# 2016ship.net
KiCad netlist of a schematic drawn in Altium Designer
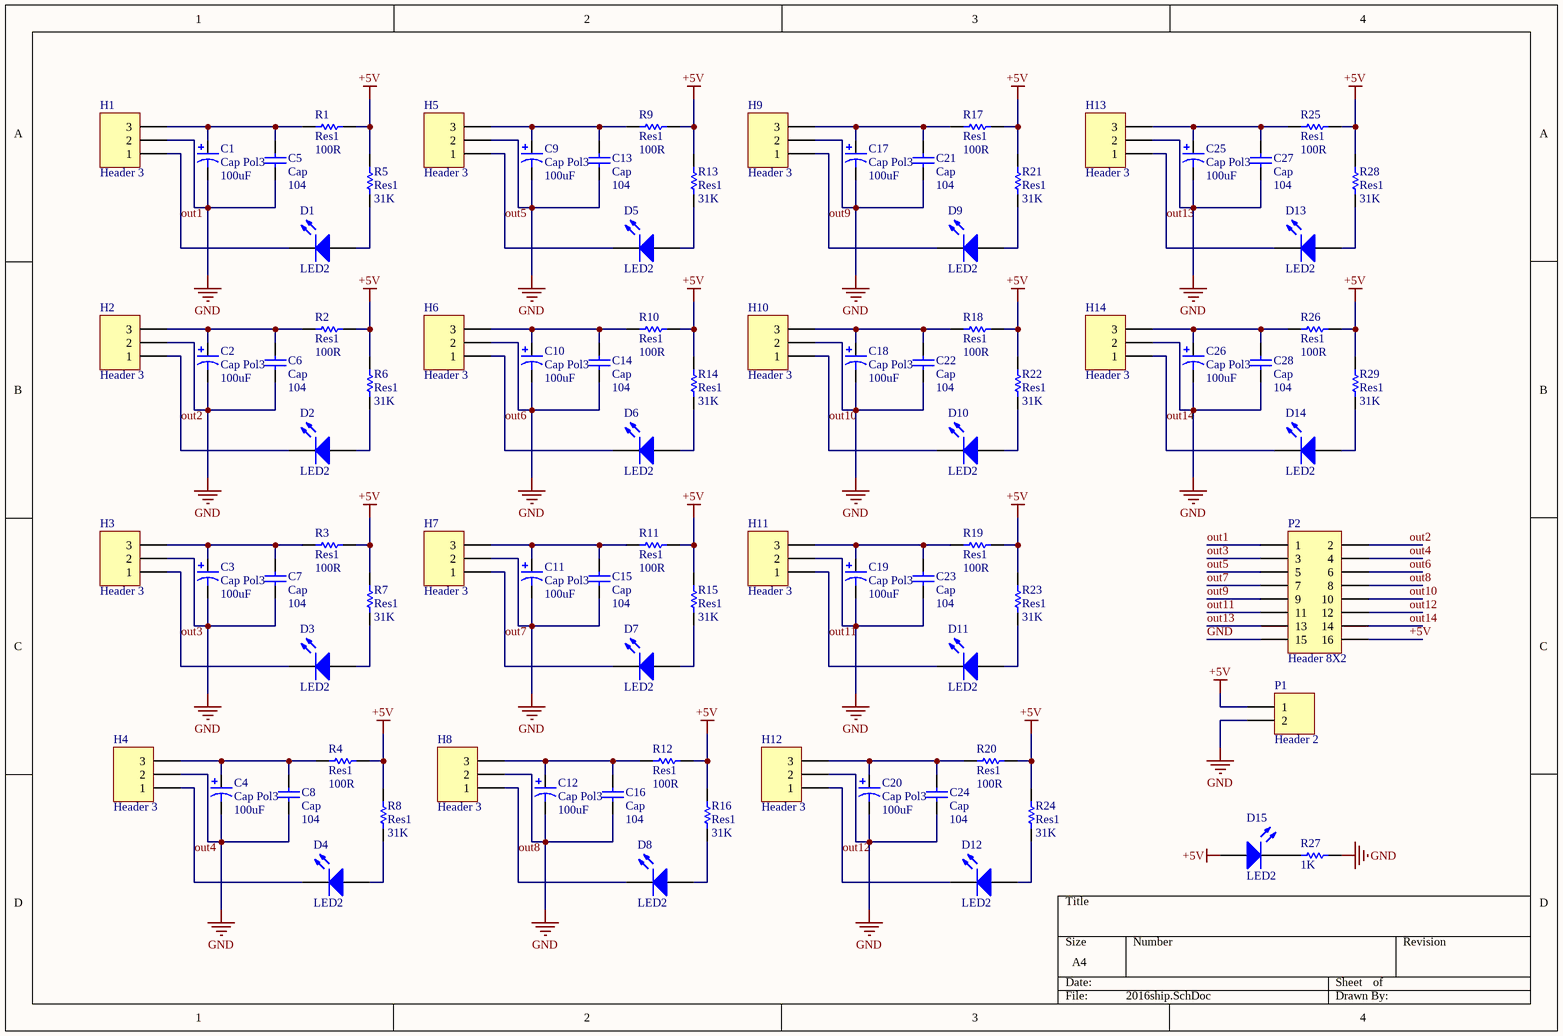
[diagram p0: 2016ship.SchDoc]

(export (version "E")
  (design (tool "Eeschema 10.0.6"))
  (components
    (comp (ref "C1")
      (value "Cap Pol3")
      (footprint "7343")
      (description "Polarized Capacitor (Surface Mount)")
      (fields (field (name "ALTIUM_VALUE") "100uF") (field (name "PUBLISHER") "Altium Limited"))
      (libsource (lib "Miscellaneous Devices") (part "Cap Pol3"))
    )
    (comp (ref "C2")
      (value "Cap Pol3")
      (footprint "7343")
      (description "Polarized Capacitor (Surface Mount)")
      (fields (field (name "ALTIUM_VALUE") "100uF") (field (name "PUBLISHER") "Altium Limited"))
      (libsource (lib "Miscellaneous Devices") (part "Cap Pol3"))
    )
    (comp (ref "C3")
      (value "Cap Pol3")
      (footprint "7343")
      (description "Polarized Capacitor (Surface Mount)")
      (fields (field (name "ALTIUM_VALUE") "100uF") (field (name "PUBLISHER") "Altium Limited"))
      (libsource (lib "Miscellaneous Devices") (part "Cap Pol3"))
    )
    (comp (ref "C4")
      (value "Cap Pol3")
      (footprint "7343")
      (description "Polarized Capacitor (Surface Mount)")
      (fields (field (name "ALTIUM_VALUE") "100uF") (field (name "PUBLISHER") "Altium Limited"))
      (libsource (lib "Miscellaneous Devices") (part "Cap Pol3"))
    )
    (comp (ref "C5")
      (value "Cap")
      (footprint "0805C")
      (description "Capacitor")
      (fields (field (name "ALTIUM_VALUE") "104") (field (name "PUBLISHER") "Altium Limited"))
      (libsource (lib "Miscellaneous Devices") (part "Cap"))
    )
    (comp (ref "C6")
      (value "Cap")
      (footprint "0805C")
      (description "Capacitor")
      (fields (field (name "ALTIUM_VALUE") "104") (field (name "PUBLISHER") "Altium Limited"))
      (libsource (lib "Miscellaneous Devices") (part "Cap"))
    )
    (comp (ref "C7")
      (value "Cap")
      (footprint "0805C")
      (description "Capacitor")
      (fields (field (name "ALTIUM_VALUE") "104") (field (name "PUBLISHER") "Altium Limited"))
      (libsource (lib "Miscellaneous Devices") (part "Cap"))
    )
    (comp (ref "C8")
      (value "Cap")
      (footprint "0805C")
      (description "Capacitor")
      (fields (field (name "ALTIUM_VALUE") "104") (field (name "PUBLISHER") "Altium Limited"))
      (libsource (lib "Miscellaneous Devices") (part "Cap"))
    )
    (comp (ref "C9")
      (value "Cap Pol3")
      (footprint "7343")
      (description "Polarized Capacitor (Surface Mount)")
      (fields (field (name "ALTIUM_VALUE") "100uF") (field (name "PUBLISHER") "Altium Limited"))
      (libsource (lib "Miscellaneous Devices") (part "Cap Pol3"))
    )
    (comp (ref "C10")
      (value "Cap Pol3")
      (footprint "7343")
      (description "Polarized Capacitor (Surface Mount)")
      (fields (field (name "ALTIUM_VALUE") "100uF") (field (name "PUBLISHER") "Altium Limited"))
      (libsource (lib "Miscellaneous Devices") (part "Cap Pol3"))
    )
    (comp (ref "C11")
      (value "Cap Pol3")
      (footprint "7343")
      (description "Polarized Capacitor (Surface Mount)")
      (fields (field (name "ALTIUM_VALUE") "100uF") (field (name "PUBLISHER") "Altium Limited"))
      (libsource (lib "Miscellaneous Devices") (part "Cap Pol3"))
    )
    (comp (ref "C12")
      (value "Cap Pol3")
      (footprint "7343")
      (description "Polarized Capacitor (Surface Mount)")
      (fields (field (name "ALTIUM_VALUE") "100uF") (field (name "PUBLISHER") "Altium Limited"))
      (libsource (lib "Miscellaneous Devices") (part "Cap Pol3"))
    )
    (comp (ref "C13")
      (value "Cap")
      (footprint "0805C")
      (description "Capacitor")
      (fields (field (name "ALTIUM_VALUE") "104") (field (name "PUBLISHER") "Altium Limited"))
      (libsource (lib "Miscellaneous Devices") (part "Cap"))
    )
    (comp (ref "C14")
      (value "Cap")
      (footprint "0805c")
      (description "Capacitor")
      (fields (field (name "ALTIUM_VALUE") "104") (field (name "PUBLISHER") "Altium Limited"))
      (libsource (lib "Miscellaneous Devices") (part "Cap"))
    )
    (comp (ref "C15")
      (value "Cap")
      (footprint "0805C")
      (description "Capacitor")
      (fields (field (name "ALTIUM_VALUE") "104") (field (name "PUBLISHER") "Altium Limited"))
      (libsource (lib "Miscellaneous Devices") (part "Cap"))
    )
    (comp (ref "C16")
      (value "Cap")
      (footprint "0805C")
      (description "Capacitor")
      (fields (field (name "ALTIUM_VALUE") "104") (field (name "PUBLISHER") "Altium Limited"))
      (libsource (lib "Miscellaneous Devices") (part "Cap"))
    )
    (comp (ref "C17")
      (value "Cap Pol3")
      (footprint "7343")
      (description "Polarized Capacitor (Surface Mount)")
      (fields (field (name "ALTIUM_VALUE") "100uF") (field (name "PUBLISHER") "Altium Limited"))
      (libsource (lib "Miscellaneous Devices") (part "Cap Pol3"))
    )
    (comp (ref "C18")
      (value "Cap Pol3")
      (footprint "7343")
      (description "Polarized Capacitor (Surface Mount)")
      (fields (field (name "ALTIUM_VALUE") "100uF") (field (name "PUBLISHER") "Altium Limited"))
      (libsource (lib "Miscellaneous Devices") (part "Cap Pol3"))
    )
    (comp (ref "C19")
      (value "Cap Pol3")
      (footprint "7343")
      (description "Polarized Capacitor (Surface Mount)")
      (fields (field (name "ALTIUM_VALUE") "100uF") (field (name "PUBLISHER") "Altium Limited"))
      (libsource (lib "Miscellaneous Devices") (part "Cap Pol3"))
    )
    (comp (ref "C20")
      (value "Cap Pol3")
      (footprint "7343")
      (description "Polarized Capacitor (Surface Mount)")
      (fields (field (name "ALTIUM_VALUE") "100uF") (field (name "PUBLISHER") "Altium Limited"))
      (libsource (lib "Miscellaneous Devices") (part "Cap Pol3"))
    )
    (comp (ref "C21")
      (value "Cap")
      (footprint "0805C")
      (description "Capacitor")
      (fields (field (name "ALTIUM_VALUE") "104") (field (name "PUBLISHER") "Altium Limited"))
      (libsource (lib "Miscellaneous Devices") (part "Cap"))
    )
    (comp (ref "C22")
      (value "Cap")
      (footprint "0805C")
      (description "Capacitor")
      (fields (field (name "ALTIUM_VALUE") "104") (field (name "PUBLISHER") "Altium Limited"))
      (libsource (lib "Miscellaneous Devices") (part "Cap"))
    )
    (comp (ref "C23")
      (value "Cap")
      (footprint "0805C")
      (description "Capacitor")
      (fields (field (name "ALTIUM_VALUE") "104") (field (name "PUBLISHER") "Altium Limited"))
      (libsource (lib "Miscellaneous Devices") (part "Cap"))
    )
    (comp (ref "C24")
      (value "Cap")
      (footprint "0805C")
      (description "Capacitor")
      (fields (field (name "ALTIUM_VALUE") "104") (field (name "PUBLISHER") "Altium Limited"))
      (libsource (lib "Miscellaneous Devices") (part "Cap"))
    )
    (comp (ref "C25")
      (value "Cap Pol3")
      (footprint "7343")
      (description "Polarized Capacitor (Surface Mount)")
      (fields (field (name "ALTIUM_VALUE") "100uF") (field (name "PUBLISHER") "Altium Limited"))
      (libsource (lib "Miscellaneous Devices") (part "Cap Pol3"))
    )
    (comp (ref "C26")
      (value "Cap Pol3")
      (footprint "7343")
      (description "Polarized Capacitor (Surface Mount)")
      (fields (field (name "ALTIUM_VALUE") "100uF") (field (name "PUBLISHER") "Altium Limited"))
      (libsource (lib "Miscellaneous Devices") (part "Cap Pol3"))
    )
    (comp (ref "C27")
      (value "Cap")
      (footprint "0805C")
      (description "Capacitor")
      (fields (field (name "ALTIUM_VALUE") "104") (field (name "PUBLISHER") "Altium Limited"))
      (libsource (lib "Miscellaneous Devices") (part "Cap"))
    )
    (comp (ref "C28")
      (value "Cap")
      (footprint "0805C")
      (description "Capacitor")
      (fields (field (name "ALTIUM_VALUE") "104") (field (name "PUBLISHER") "Altium Limited"))
      (libsource (lib "Miscellaneous Devices") (part "Cap"))
    )
    (comp (ref "D1")
      (value "LED2")
      (footprint "LED-0805")
      (description "Typical RED, GREEN, YELLOW, AMBER GaAs LED")
      (fields (field (name "PUBLISHER") "Altium Limited"))
      (libsource (lib "Miscellaneous Devices") (part "LED2"))
    )
    (comp (ref "D2")
      (value "LED2")
      (footprint "LED-0805")
      (description "Typical RED, GREEN, YELLOW, AMBER GaAs LED")
      (fields (field (name "PUBLISHER") "Altium Limited"))
      (libsource (lib "Miscellaneous Devices") (part "LED2"))
    )
    (comp (ref "D3")
      (value "LED2")
      (footprint "LED-0805")
      (description "Typical RED, GREEN, YELLOW, AMBER GaAs LED")
      (fields (field (name "PUBLISHER") "Altium Limited"))
      (libsource (lib "Miscellaneous Devices") (part "LED2"))
    )
    (comp (ref "D4")
      (value "LED2")
      (footprint "LED-0805")
      (description "Typical RED, GREEN, YELLOW, AMBER GaAs LED")
      (fields (field (name "PUBLISHER") "Altium Limited"))
      (libsource (lib "Miscellaneous Devices") (part "LED2"))
    )
    (comp (ref "D5")
      (value "LED2")
      (footprint "LED-0805")
      (description "Typical RED, GREEN, YELLOW, AMBER GaAs LED")
      (fields (field (name "PUBLISHER") "Altium Limited"))
      (libsource (lib "Miscellaneous Devices") (part "LED2"))
    )
    (comp (ref "D6")
      (value "LED2")
      (footprint "LED-0805")
      (description "Typical RED, GREEN, YELLOW, AMBER GaAs LED")
      (fields (field (name "PUBLISHER") "Altium Limited"))
      (libsource (lib "Miscellaneous Devices") (part "LED2"))
    )
    (comp (ref "D7")
      (value "LED2")
      (footprint "LED-0805")
      (description "Typical RED, GREEN, YELLOW, AMBER GaAs LED")
      (fields (field (name "PUBLISHER") "Altium Limited"))
      (libsource (lib "Miscellaneous Devices") (part "LED2"))
    )
    (comp (ref "D8")
      (value "LED2")
      (footprint "LED-0805")
      (description "Typical RED, GREEN, YELLOW, AMBER GaAs LED")
      (fields (field (name "PUBLISHER") "Altium Limited"))
      (libsource (lib "Miscellaneous Devices") (part "LED2"))
    )
    (comp (ref "D9")
      (value "LED2")
      (footprint "LED-0805")
      (description "Typical RED, GREEN, YELLOW, AMBER GaAs LED")
      (fields (field (name "PUBLISHER") "Altium Limited"))
      (libsource (lib "Miscellaneous Devices") (part "LED2"))
    )
    (comp (ref "D10")
      (value "LED2")
      (footprint "LED-0805")
      (description "Typical RED, GREEN, YELLOW, AMBER GaAs LED")
      (fields (field (name "PUBLISHER") "Altium Limited"))
      (libsource (lib "Miscellaneous Devices") (part "LED2"))
    )
    (comp (ref "D11")
      (value "LED2")
      (footprint "LED-0805")
      (description "Typical RED, GREEN, YELLOW, AMBER GaAs LED")
      (fields (field (name "PUBLISHER") "Altium Limited"))
      (libsource (lib "Miscellaneous Devices") (part "LED2"))
    )
    (comp (ref "D12")
      (value "LED2")
      (footprint "LED-0805")
      (description "Typical RED, GREEN, YELLOW, AMBER GaAs LED")
      (fields (field (name "PUBLISHER") "Altium Limited"))
      (libsource (lib "Miscellaneous Devices") (part "LED2"))
    )
    (comp (ref "D13")
      (value "LED2")
      (footprint "LED-0805")
      (description "Typical RED, GREEN, YELLOW, AMBER GaAs LED")
      (fields (field (name "PUBLISHER") "Altium Limited"))
      (libsource (lib "Miscellaneous Devices") (part "LED2"))
    )
    (comp (ref "D14")
      (value "LED2")
      (footprint "LED-0805")
      (description "Typical RED, GREEN, YELLOW, AMBER GaAs LED")
      (fields (field (name "PUBLISHER") "Altium Limited"))
      (libsource (lib "Miscellaneous Devices") (part "LED2"))
    )
    (comp (ref "D15")
      (value "LED2")
      (footprint "LED-0805")
      (description "Typical RED, GREEN, YELLOW, AMBER GaAs LED")
      (fields (field (name "PUBLISHER") "Altium Limited"))
      (libsource (lib "Miscellaneous Devices") (part "LED2"))
    )
    (comp (ref "H1")
      (value "Header 3")
      (footprint "HDR1X3")
      (description "Header, 3-Pin")
      (fields (field (name "PUBLISHER") "Altium Limited"))
      (libsource (lib "Miscellaneous Connectors") (part "Header 3"))
    )
    (comp (ref "H2")
      (value "Header 3")
      (footprint "HDR1X3")
      (description "Header, 3-Pin")
      (fields (field (name "PUBLISHER") "Altium Limited"))
      (libsource (lib "Miscellaneous Connectors") (part "Header 3"))
    )
    (comp (ref "H3")
      (value "Header 3")
      (footprint "HDR1X3")
      (description "Header, 3-Pin")
      (fields (field (name "PUBLISHER") "Altium Limited"))
      (libsource (lib "Miscellaneous Connectors") (part "Header 3"))
    )
    (comp (ref "H4")
      (value "Header 3")
      (footprint "HDR1X3")
      (description "Header, 3-Pin")
      (fields (field (name "PUBLISHER") "Altium Limited"))
      (libsource (lib "Miscellaneous Connectors") (part "Header 3"))
    )
    (comp (ref "H5")
      (value "Header 3")
      (footprint "HDR1X3")
      (description "Header, 3-Pin")
      (fields (field (name "PUBLISHER") "Altium Limited"))
      (libsource (lib "Miscellaneous Connectors") (part "Header 3"))
    )
    (comp (ref "H6")
      (value "Header 3")
      (footprint "HDR1X3")
      (description "Header, 3-Pin")
      (fields (field (name "PUBLISHER") "Altium Limited"))
      (libsource (lib "Miscellaneous Connectors") (part "Header 3"))
    )
    (comp (ref "H7")
      (value "Header 3")
      (footprint "HDR1X3")
      (description "Header, 3-Pin")
      (fields (field (name "PUBLISHER") "Altium Limited"))
      (libsource (lib "Miscellaneous Connectors") (part "Header 3"))
    )
    (comp (ref "H8")
      (value "Header 3")
      (footprint "HDR1X3")
      (description "Header, 3-Pin")
      (fields (field (name "PUBLISHER") "Altium Limited"))
      (libsource (lib "Miscellaneous Connectors") (part "Header 3"))
    )
    (comp (ref "H9")
      (value "Header 3")
      (footprint "HDR1X3")
      (description "Header, 3-Pin")
      (fields (field (name "PUBLISHER") "Altium Limited"))
      (libsource (lib "Miscellaneous Connectors") (part "Header 3"))
    )
    (comp (ref "H10")
      (value "Header 3")
      (footprint "HDR1X3")
      (description "Header, 3-Pin")
      (fields (field (name "PUBLISHER") "Altium Limited"))
      (libsource (lib "Miscellaneous Connectors") (part "Header 3"))
    )
    (comp (ref "H11")
      (value "Header 3")
      (footprint "HDR1X3")
      (description "Header, 3-Pin")
      (fields (field (name "PUBLISHER") "Altium Limited"))
      (libsource (lib "Miscellaneous Connectors") (part "Header 3"))
    )
    (comp (ref "H12")
      (value "Header 3")
      (footprint "HDR1X3")
      (description "Header, 3-Pin")
      (fields (field (name "PUBLISHER") "Altium Limited"))
      (libsource (lib "Miscellaneous Connectors") (part "Header 3"))
    )
    (comp (ref "H13")
      (value "Header 3")
      (footprint "HDR1X3")
      (description "Header, 3-Pin")
      (fields (field (name "PUBLISHER") "Altium Limited"))
      (libsource (lib "Miscellaneous Connectors") (part "Header 3"))
    )
    (comp (ref "H14")
      (value "Header 3")
      (footprint "HDR1X3")
      (description "Header, 3-Pin")
      (fields (field (name "PUBLISHER") "Altium Limited"))
      (libsource (lib "Miscellaneous Connectors") (part "Header 3"))
    )
    (comp (ref "P1")
      (value "Header 2")
      (footprint "HDR1X2")
      (description "Header, 2-Pin")
      (fields (field (name "PUBLISHER") "Altium Limited"))
      (libsource (lib "Miscellaneous Connectors") (part "Header 2"))
    )
    (comp (ref "P2")
      (value "Header 8X2")
      (footprint "HDR2X8")
      (description "Header, 8-Pin, Dual row")
      (fields (field (name "PUBLISHER") "Altium Limited"))
      (libsource (lib "Miscellaneous Connectors") (part "Header 8X2"))
    )
    (comp (ref "R1")
      (value "Res1")
      (footprint "0805R")
      (description "Resistor")
      (fields (field (name "ALTIUM_VALUE") "100R") (field (name "PUBLISHER") "Altium Limited"))
      (libsource (lib "Miscellaneous Devices") (part "Res1"))
    )
    (comp (ref "R2")
      (value "Res1")
      (footprint "0805R")
      (description "Resistor")
      (fields (field (name "ALTIUM_VALUE") "100R") (field (name "PUBLISHER") "Altium Limited"))
      (libsource (lib "Miscellaneous Devices") (part "Res1"))
    )
    (comp (ref "R3")
      (value "Res1")
      (footprint "0805R")
      (description "Resistor")
      (fields (field (name "ALTIUM_VALUE") "100R") (field (name "PUBLISHER") "Altium Limited"))
      (libsource (lib "Miscellaneous Devices") (part "Res1"))
    )
    (comp (ref "R4")
      (value "Res1")
      (footprint "0805R")
      (description "Resistor")
      (fields (field (name "ALTIUM_VALUE") "100R") (field (name "PUBLISHER") "Altium Limited"))
      (libsource (lib "Miscellaneous Devices") (part "Res1"))
    )
    (comp (ref "R5")
      (value "Res1")
      (footprint "0805R")
      (description "Resistor")
      (fields (field (name "ALTIUM_VALUE") "31K") (field (name "PUBLISHER") "Altium Limited"))
      (libsource (lib "Miscellaneous Devices") (part "Res1"))
    )
    (comp (ref "R6")
      (value "Res1")
      (footprint "0805R")
      (description "Resistor")
      (fields (field (name "ALTIUM_VALUE") "31K") (field (name "PUBLISHER") "Altium Limited"))
      (libsource (lib "Miscellaneous Devices") (part "Res1"))
    )
    (comp (ref "R7")
      (value "Res1")
      (footprint "0805R")
      (description "Resistor")
      (fields (field (name "ALTIUM_VALUE") "31K") (field (name "PUBLISHER") "Altium Limited"))
      (libsource (lib "Miscellaneous Devices") (part "Res1"))
    )
    (comp (ref "R8")
      (value "Res1")
      (footprint "0805R")
      (description "Resistor")
      (fields (field (name "ALTIUM_VALUE") "31K") (field (name "PUBLISHER") "Altium Limited"))
      (libsource (lib "Miscellaneous Devices") (part "Res1"))
    )
    (comp (ref "R9")
      (value "Res1")
      (footprint "0805R")
      (description "Resistor")
      (fields (field (name "ALTIUM_VALUE") "100R") (field (name "PUBLISHER") "Altium Limited"))
      (libsource (lib "Miscellaneous Devices") (part "Res1"))
    )
    (comp (ref "R10")
      (value "Res1")
      (footprint "0805R")
      (description "Resistor")
      (fields (field (name "ALTIUM_VALUE") "100R") (field (name "PUBLISHER") "Altium Limited"))
      (libsource (lib "Miscellaneous Devices") (part "Res1"))
    )
    (comp (ref "R11")
      (value "Res1")
      (footprint "0805R")
      (description "Resistor")
      (fields (field (name "ALTIUM_VALUE") "100R") (field (name "PUBLISHER") "Altium Limited"))
      (libsource (lib "Miscellaneous Devices") (part "Res1"))
    )
    (comp (ref "R12")
      (value "Res1")
      (footprint "0805R")
      (description "Resistor")
      (fields (field (name "ALTIUM_VALUE") "100R") (field (name "PUBLISHER") "Altium Limited"))
      (libsource (lib "Miscellaneous Devices") (part "Res1"))
    )
    (comp (ref "R13")
      (value "Res1")
      (footprint "0805R")
      (description "Resistor")
      (fields (field (name "ALTIUM_VALUE") "31K") (field (name "PUBLISHER") "Altium Limited"))
      (libsource (lib "Miscellaneous Devices") (part "Res1"))
    )
    (comp (ref "R14")
      (value "Res1")
      (footprint "0805R")
      (description "Resistor")
      (fields (field (name "ALTIUM_VALUE") "31K") (field (name "PUBLISHER") "Altium Limited"))
      (libsource (lib "Miscellaneous Devices") (part "Res1"))
    )
    (comp (ref "R15")
      (value "Res1")
      (footprint "0805R")
      (description "Resistor")
      (fields (field (name "ALTIUM_VALUE") "31K") (field (name "PUBLISHER") "Altium Limited"))
      (libsource (lib "Miscellaneous Devices") (part "Res1"))
    )
    (comp (ref "R16")
      (value "Res1")
      (footprint "0805R")
      (description "Resistor")
      (fields (field (name "ALTIUM_VALUE") "31K") (field (name "PUBLISHER") "Altium Limited"))
      (libsource (lib "Miscellaneous Devices") (part "Res1"))
    )
    (comp (ref "R17")
      (value "Res1")
      (footprint "0805R")
      (description "Resistor")
      (fields (field (name "ALTIUM_VALUE") "100R") (field (name "PUBLISHER") "Altium Limited"))
      (libsource (lib "Miscellaneous Devices") (part "Res1"))
    )
    (comp (ref "R18")
      (value "Res1")
      (footprint "0805R")
      (description "Resistor")
      (fields (field (name "ALTIUM_VALUE") "100R") (field (name "PUBLISHER") "Altium Limited"))
      (libsource (lib "Miscellaneous Devices") (part "Res1"))
    )
    (comp (ref "R19")
      (value "Res1")
      (footprint "0805R")
      (description "Resistor")
      (fields (field (name "ALTIUM_VALUE") "100R") (field (name "PUBLISHER") "Altium Limited"))
      (libsource (lib "Miscellaneous Devices") (part "Res1"))
    )
    (comp (ref "R20")
      (value "Res1")
      (footprint "0805R")
      (description "Resistor")
      (fields (field (name "ALTIUM_VALUE") "100R") (field (name "PUBLISHER") "Altium Limited"))
      (libsource (lib "Miscellaneous Devices") (part "Res1"))
    )
    (comp (ref "R21")
      (value "Res1")
      (footprint "0805R")
      (description "Resistor")
      (fields (field (name "ALTIUM_VALUE") "31K") (field (name "PUBLISHER") "Altium Limited"))
      (libsource (lib "Miscellaneous Devices") (part "Res1"))
    )
    (comp (ref "R22")
      (value "Res1")
      (footprint "0805R")
      (description "Resistor")
      (fields (field (name "ALTIUM_VALUE") "31K") (field (name "PUBLISHER") "Altium Limited"))
      (libsource (lib "Miscellaneous Devices") (part "Res1"))
    )
    (comp (ref "R23")
      (value "Res1")
      (footprint "0805R")
      (description "Resistor")
      (fields (field (name "ALTIUM_VALUE") "31K") (field (name "PUBLISHER") "Altium Limited"))
      (libsource (lib "Miscellaneous Devices") (part "Res1"))
    )
    (comp (ref "R24")
      (value "Res1")
      (footprint "0805R")
      (description "Resistor")
      (fields (field (name "ALTIUM_VALUE") "31K") (field (name "PUBLISHER") "Altium Limited"))
      (libsource (lib "Miscellaneous Devices") (part "Res1"))
    )
    (comp (ref "R25")
      (value "Res1")
      (footprint "0805R")
      (description "Resistor")
      (fields (field (name "ALTIUM_VALUE") "100R") (field (name "PUBLISHER") "Altium Limited"))
      (libsource (lib "Miscellaneous Devices") (part "Res1"))
    )
    (comp (ref "R26")
      (value "Res1")
      (footprint "0805R")
      (description "Resistor")
      (fields (field (name "ALTIUM_VALUE") "100R") (field (name "PUBLISHER") "Altium Limited"))
      (libsource (lib "Miscellaneous Devices") (part "Res1"))
    )
    (comp (ref "R27")
      (value "1K")
      (footprint "0805R")
      (description "Resistor")
      (fields (field (name "Comment") "Res1") (field (name "PUBLISHER") "Altium Limited"))
      (libsource (lib "Miscellaneous Devices") (part "Res1"))
    )
    (comp (ref "R28")
      (value "Res1")
      (footprint "0805R")
      (description "Resistor")
      (fields (field (name "ALTIUM_VALUE") "31K") (field (name "PUBLISHER") "Altium Limited"))
      (libsource (lib "Miscellaneous Devices") (part "Res1"))
    )
    (comp (ref "R29")
      (value "Res1")
      (footprint "0805R")
      (description "Resistor")
      (fields (field (name "ALTIUM_VALUE") "31K") (field (name "PUBLISHER") "Altium Limited"))
      (libsource (lib "Miscellaneous Devices") (part "Res1"))
    )
  )
  (nets
    (net (code "1") (name "+5V") (class "Default")
      (node (ref "D15") (pin "1") (pinfunction "A_1") (pintype "passive"))
      (node (ref "P1") (pin "1") (pinfunction "1_1") (pintype "passive"))
      (node (ref "P2") (pin "16") (pinfunction "16_16") (pintype "passive"))
      (node (ref "R1") (pin "2") (pinfunction "2_2") (pintype "passive"))
      (node (ref "R10") (pin "2") (pinfunction "2_2") (pintype "passive"))
      (node (ref "R11") (pin "2") (pinfunction "2_2") (pintype "passive"))
      (node (ref "R12") (pin "2") (pinfunction "2_2") (pintype "passive"))
      (node (ref "R13") (pin "2") (pinfunction "2_2") (pintype "passive"))
      (node (ref "R14") (pin "2") (pinfunction "2_2") (pintype "passive"))
      (node (ref "R15") (pin "2") (pinfunction "2_2") (pintype "passive"))
      (node (ref "R16") (pin "2") (pinfunction "2_2") (pintype "passive"))
      (node (ref "R17") (pin "2") (pinfunction "2_2") (pintype "passive"))
      (node (ref "R18") (pin "2") (pinfunction "2_2") (pintype "passive"))
      (node (ref "R19") (pin "2") (pinfunction "2_2") (pintype "passive"))
      (node (ref "R2") (pin "2") (pinfunction "2_2") (pintype "passive"))
      (node (ref "R20") (pin "2") (pinfunction "2_2") (pintype "passive"))
      (node (ref "R21") (pin "2") (pinfunction "2_2") (pintype "passive"))
      (node (ref "R22") (pin "2") (pinfunction "2_2") (pintype "passive"))
      (node (ref "R23") (pin "2") (pinfunction "2_2") (pintype "passive"))
      (node (ref "R24") (pin "2") (pinfunction "2_2") (pintype "passive"))
      (node (ref "R25") (pin "2") (pinfunction "2_2") (pintype "passive"))
      (node (ref "R26") (pin "2") (pinfunction "2_2") (pintype "passive"))
      (node (ref "R28") (pin "2") (pinfunction "2_2") (pintype "passive"))
      (node (ref "R29") (pin "2") (pinfunction "2_2") (pintype "passive"))
      (node (ref "R3") (pin "2") (pinfunction "2_2") (pintype "passive"))
      (node (ref "R4") (pin "2") (pinfunction "2_2") (pintype "passive"))
      (node (ref "R5") (pin "2") (pinfunction "2_2") (pintype "passive"))
      (node (ref "R6") (pin "2") (pinfunction "2_2") (pintype "passive"))
      (node (ref "R7") (pin "2") (pinfunction "2_2") (pintype "passive"))
      (node (ref "R8") (pin "2") (pinfunction "2_2") (pintype "passive"))
      (node (ref "R9") (pin "2") (pinfunction "2_2") (pintype "passive"))
    )
    (net (code "2") (name "/out1") (class "Default")
      (node (ref "D1") (pin "2") (pinfunction "K_2") (pintype "passive"))
      (node (ref "H1") (pin "1") (pinfunction "1_1") (pintype "passive"))
      (node (ref "P2") (pin "1") (pinfunction "1_1") (pintype "passive"))
    )
    (net (code "3") (name "/out2") (class "Default")
      (node (ref "D2") (pin "2") (pinfunction "K_2") (pintype "passive"))
      (node (ref "H2") (pin "1") (pinfunction "1_1") (pintype "passive"))
      (node (ref "P2") (pin "2") (pinfunction "2_2") (pintype "passive"))
    )
    (net (code "4") (name "/out3") (class "Default")
      (node (ref "D3") (pin "2") (pinfunction "K_2") (pintype "passive"))
      (node (ref "H3") (pin "1") (pinfunction "1_1") (pintype "passive"))
      (node (ref "P2") (pin "3") (pinfunction "3_3") (pintype "passive"))
    )
    (net (code "5") (name "/out4") (class "Default")
      (node (ref "D4") (pin "2") (pinfunction "K_2") (pintype "passive"))
      (node (ref "H4") (pin "1") (pinfunction "1_1") (pintype "passive"))
      (node (ref "P2") (pin "4") (pinfunction "4_4") (pintype "passive"))
    )
    (net (code "6") (name "/out5") (class "Default")
      (node (ref "D5") (pin "2") (pinfunction "K_2") (pintype "passive"))
      (node (ref "H5") (pin "1") (pinfunction "1_1") (pintype "passive"))
      (node (ref "P2") (pin "5") (pinfunction "5_5") (pintype "passive"))
    )
    (net (code "7") (name "/out6") (class "Default")
      (node (ref "D6") (pin "2") (pinfunction "K_2") (pintype "passive"))
      (node (ref "H6") (pin "1") (pinfunction "1_1") (pintype "passive"))
      (node (ref "P2") (pin "6") (pinfunction "6_6") (pintype "passive"))
    )
    (net (code "8") (name "/out7") (class "Default")
      (node (ref "D7") (pin "2") (pinfunction "K_2") (pintype "passive"))
      (node (ref "H7") (pin "1") (pinfunction "1_1") (pintype "passive"))
      (node (ref "P2") (pin "7") (pinfunction "7_7") (pintype "passive"))
    )
    (net (code "9") (name "/out8") (class "Default")
      (node (ref "D8") (pin "2") (pinfunction "K_2") (pintype "passive"))
      (node (ref "H8") (pin "1") (pinfunction "1_1") (pintype "passive"))
      (node (ref "P2") (pin "8") (pinfunction "8_8") (pintype "passive"))
    )
    (net (code "10") (name "/out9") (class "Default")
      (node (ref "D9") (pin "2") (pinfunction "K_2") (pintype "passive"))
      (node (ref "H9") (pin "1") (pinfunction "1_1") (pintype "passive"))
      (node (ref "P2") (pin "9") (pinfunction "9_9") (pintype "passive"))
    )
    (net (code "11") (name "/out10") (class "Default")
      (node (ref "D10") (pin "2") (pinfunction "K_2") (pintype "passive"))
      (node (ref "H10") (pin "1") (pinfunction "1_1") (pintype "passive"))
      (node (ref "P2") (pin "10") (pinfunction "10_10") (pintype "passive"))
    )
    (net (code "12") (name "/out11") (class "Default")
      (node (ref "D11") (pin "2") (pinfunction "K_2") (pintype "passive"))
      (node (ref "H11") (pin "1") (pinfunction "1_1") (pintype "passive"))
      (node (ref "P2") (pin "11") (pinfunction "11_11") (pintype "passive"))
    )
    (net (code "13") (name "/out12") (class "Default")
      (node (ref "D12") (pin "2") (pinfunction "K_2") (pintype "passive"))
      (node (ref "H12") (pin "1") (pinfunction "1_1") (pintype "passive"))
      (node (ref "P2") (pin "12") (pinfunction "12_12") (pintype "passive"))
    )
    (net (code "14") (name "/out13") (class "Default")
      (node (ref "D13") (pin "2") (pinfunction "K_2") (pintype "passive"))
      (node (ref "H13") (pin "1") (pinfunction "1_1") (pintype "passive"))
      (node (ref "P2") (pin "13") (pinfunction "13_13") (pintype "passive"))
    )
    (net (code "15") (name "/out14") (class "Default")
      (node (ref "D14") (pin "2") (pinfunction "K_2") (pintype "passive"))
      (node (ref "H14") (pin "1") (pinfunction "1_1") (pintype "passive"))
      (node (ref "P2") (pin "14") (pinfunction "14_14") (pintype "passive"))
    )
    (net (code "16") (name "GND") (class "Default")
      (node (ref "C1") (pin "2") (pinfunction "2_2") (pintype "passive"))
      (node (ref "C10") (pin "2") (pinfunction "2_2") (pintype "passive"))
      (node (ref "C11") (pin "2") (pinfunction "2_2") (pintype "passive"))
      (node (ref "C12") (pin "2") (pinfunction "2_2") (pintype "passive"))
      (node (ref "C13") (pin "1") (pinfunction "1_1") (pintype "passive"))
      (node (ref "C14") (pin "1") (pinfunction "1_1") (pintype "passive"))
      (node (ref "C15") (pin "1") (pinfunction "1_1") (pintype "passive"))
      (node (ref "C16") (pin "1") (pinfunction "1_1") (pintype "passive"))
      (node (ref "C17") (pin "2") (pinfunction "2_2") (pintype "passive"))
      (node (ref "C18") (pin "2") (pinfunction "2_2") (pintype "passive"))
      (node (ref "C19") (pin "2") (pinfunction "2_2") (pintype "passive"))
      (node (ref "C2") (pin "2") (pinfunction "2_2") (pintype "passive"))
      (node (ref "C20") (pin "2") (pinfunction "2_2") (pintype "passive"))
      (node (ref "C21") (pin "1") (pinfunction "1_1") (pintype "passive"))
      (node (ref "C22") (pin "1") (pinfunction "1_1") (pintype "passive"))
      (node (ref "C23") (pin "1") (pinfunction "1_1") (pintype "passive"))
      (node (ref "C24") (pin "1") (pinfunction "1_1") (pintype "passive"))
      (node (ref "C25") (pin "2") (pinfunction "2_2") (pintype "passive"))
      (node (ref "C26") (pin "2") (pinfunction "2_2") (pintype "passive"))
      (node (ref "C27") (pin "1") (pinfunction "1_1") (pintype "passive"))
      (node (ref "C28") (pin "1") (pinfunction "1_1") (pintype "passive"))
      (node (ref "C3") (pin "2") (pinfunction "2_2") (pintype "passive"))
      (node (ref "C4") (pin "2") (pinfunction "2_2") (pintype "passive"))
      (node (ref "C5") (pin "1") (pinfunction "1_1") (pintype "passive"))
      (node (ref "C6") (pin "1") (pinfunction "1_1") (pintype "passive"))
      (node (ref "C7") (pin "1") (pinfunction "1_1") (pintype "passive"))
      (node (ref "C8") (pin "1") (pinfunction "1_1") (pintype "passive"))
      (node (ref "C9") (pin "2") (pinfunction "2_2") (pintype "passive"))
      (node (ref "H1") (pin "2") (pinfunction "2_2") (pintype "passive"))
      (node (ref "H10") (pin "2") (pinfunction "2_2") (pintype "passive"))
      (node (ref "H11") (pin "2") (pinfunction "2_2") (pintype "passive"))
      (node (ref "H12") (pin "2") (pinfunction "2_2") (pintype "passive"))
      (node (ref "H13") (pin "2") (pinfunction "2_2") (pintype "passive"))
      (node (ref "H14") (pin "2") (pinfunction "2_2") (pintype "passive"))
      (node (ref "H2") (pin "2") (pinfunction "2_2") (pintype "passive"))
      (node (ref "H3") (pin "2") (pinfunction "2_2") (pintype "passive"))
      (node (ref "H4") (pin "2") (pinfunction "2_2") (pintype "passive"))
      (node (ref "H5") (pin "2") (pinfunction "2_2") (pintype "passive"))
      (node (ref "H6") (pin "2") (pinfunction "2_2") (pintype "passive"))
      (node (ref "H7") (pin "2") (pinfunction "2_2") (pintype "passive"))
      (node (ref "H8") (pin "2") (pinfunction "2_2") (pintype "passive"))
      (node (ref "H9") (pin "2") (pinfunction "2_2") (pintype "passive"))
      (node (ref "P1") (pin "2") (pinfunction "2_2") (pintype "passive"))
      (node (ref "P2") (pin "15") (pinfunction "15_15") (pintype "passive"))
      (node (ref "R27") (pin "1") (pinfunction "1_1") (pintype "passive"))
    )
    (net (code "17") (name "Net-(C1-Pad1)") (class "Default")
      (node (ref "C1") (pin "1") (pinfunction "1_1") (pintype "passive"))
      (node (ref "C5") (pin "2") (pinfunction "2_2") (pintype "passive"))
      (node (ref "H1") (pin "3") (pinfunction "3_3") (pintype "passive"))
      (node (ref "R1") (pin "1") (pinfunction "1_1") (pintype "passive"))
    )
    (net (code "18") (name "Net-(C2-Pad1)") (class "Default")
      (node (ref "C2") (pin "1") (pinfunction "1_1") (pintype "passive"))
      (node (ref "C6") (pin "2") (pinfunction "2_2") (pintype "passive"))
      (node (ref "H2") (pin "3") (pinfunction "3_3") (pintype "passive"))
      (node (ref "R2") (pin "1") (pinfunction "1_1") (pintype "passive"))
    )
    (net (code "19") (name "Net-(C3-Pad1)") (class "Default")
      (node (ref "C3") (pin "1") (pinfunction "1_1") (pintype "passive"))
      (node (ref "C7") (pin "2") (pinfunction "2_2") (pintype "passive"))
      (node (ref "H3") (pin "3") (pinfunction "3_3") (pintype "passive"))
      (node (ref "R3") (pin "1") (pinfunction "1_1") (pintype "passive"))
    )
    (net (code "20") (name "Net-(C4-Pad1)") (class "Default")
      (node (ref "C4") (pin "1") (pinfunction "1_1") (pintype "passive"))
      (node (ref "C8") (pin "2") (pinfunction "2_2") (pintype "passive"))
      (node (ref "H4") (pin "3") (pinfunction "3_3") (pintype "passive"))
      (node (ref "R4") (pin "1") (pinfunction "1_1") (pintype "passive"))
    )
    (net (code "21") (name "Net-(C10-Pad1)") (class "Default")
      (node (ref "C10") (pin "1") (pinfunction "1_1") (pintype "passive"))
      (node (ref "C14") (pin "2") (pinfunction "2_2") (pintype "passive"))
      (node (ref "H6") (pin "3") (pinfunction "3_3") (pintype "passive"))
      (node (ref "R10") (pin "1") (pinfunction "1_1") (pintype "passive"))
    )
    (net (code "22") (name "Net-(C11-Pad1)") (class "Default")
      (node (ref "C11") (pin "1") (pinfunction "1_1") (pintype "passive"))
      (node (ref "C15") (pin "2") (pinfunction "2_2") (pintype "passive"))
      (node (ref "H7") (pin "3") (pinfunction "3_3") (pintype "passive"))
      (node (ref "R11") (pin "1") (pinfunction "1_1") (pintype "passive"))
    )
    (net (code "23") (name "Net-(C12-Pad1)") (class "Default")
      (node (ref "C12") (pin "1") (pinfunction "1_1") (pintype "passive"))
      (node (ref "C16") (pin "2") (pinfunction "2_2") (pintype "passive"))
      (node (ref "H8") (pin "3") (pinfunction "3_3") (pintype "passive"))
      (node (ref "R12") (pin "1") (pinfunction "1_1") (pintype "passive"))
    )
    (net (code "24") (name "Net-(C13-Pad2)") (class "Default")
      (node (ref "C13") (pin "2") (pinfunction "2_2") (pintype "passive"))
      (node (ref "C9") (pin "1") (pinfunction "1_1") (pintype "passive"))
      (node (ref "H5") (pin "3") (pinfunction "3_3") (pintype "passive"))
      (node (ref "R9") (pin "1") (pinfunction "1_1") (pintype "passive"))
    )
    (net (code "25") (name "Net-(C17-Pad1)") (class "Default")
      (node (ref "C17") (pin "1") (pinfunction "1_1") (pintype "passive"))
      (node (ref "C21") (pin "2") (pinfunction "2_2") (pintype "passive"))
      (node (ref "H9") (pin "3") (pinfunction "3_3") (pintype "passive"))
      (node (ref "R17") (pin "1") (pinfunction "1_1") (pintype "passive"))
    )
    (net (code "26") (name "Net-(C18-Pad1)") (class "Default")
      (node (ref "C18") (pin "1") (pinfunction "1_1") (pintype "passive"))
      (node (ref "C22") (pin "2") (pinfunction "2_2") (pintype "passive"))
      (node (ref "H10") (pin "3") (pinfunction "3_3") (pintype "passive"))
      (node (ref "R18") (pin "1") (pinfunction "1_1") (pintype "passive"))
    )
    (net (code "27") (name "Net-(C19-Pad1)") (class "Default")
      (node (ref "C19") (pin "1") (pinfunction "1_1") (pintype "passive"))
      (node (ref "C23") (pin "2") (pinfunction "2_2") (pintype "passive"))
      (node (ref "H11") (pin "3") (pinfunction "3_3") (pintype "passive"))
      (node (ref "R19") (pin "1") (pinfunction "1_1") (pintype "passive"))
    )
    (net (code "28") (name "Net-(C20-Pad1)") (class "Default")
      (node (ref "C20") (pin "1") (pinfunction "1_1") (pintype "passive"))
      (node (ref "C24") (pin "2") (pinfunction "2_2") (pintype "passive"))
      (node (ref "H12") (pin "3") (pinfunction "3_3") (pintype "passive"))
      (node (ref "R20") (pin "1") (pinfunction "1_1") (pintype "passive"))
    )
    (net (code "29") (name "Net-(C25-Pad1)") (class "Default")
      (node (ref "C25") (pin "1") (pinfunction "1_1") (pintype "passive"))
      (node (ref "C27") (pin "2") (pinfunction "2_2") (pintype "passive"))
      (node (ref "H13") (pin "3") (pinfunction "3_3") (pintype "passive"))
      (node (ref "R25") (pin "1") (pinfunction "1_1") (pintype "passive"))
    )
    (net (code "30") (name "Net-(C26-Pad1)") (class "Default")
      (node (ref "C26") (pin "1") (pinfunction "1_1") (pintype "passive"))
      (node (ref "C28") (pin "2") (pinfunction "2_2") (pintype "passive"))
      (node (ref "H14") (pin "3") (pinfunction "3_3") (pintype "passive"))
      (node (ref "R26") (pin "1") (pinfunction "1_1") (pintype "passive"))
    )
    (net (code "31") (name "Net-(D1-A)") (class "Default")
      (node (ref "D1") (pin "1") (pinfunction "A_1") (pintype "passive"))
      (node (ref "R5") (pin "1") (pinfunction "1_1") (pintype "passive"))
    )
    (net (code "32") (name "Net-(D2-A)") (class "Default")
      (node (ref "D2") (pin "1") (pinfunction "A_1") (pintype "passive"))
      (node (ref "R6") (pin "1") (pinfunction "1_1") (pintype "passive"))
    )
    (net (code "33") (name "Net-(D3-A)") (class "Default")
      (node (ref "D3") (pin "1") (pinfunction "A_1") (pintype "passive"))
      (node (ref "R7") (pin "1") (pinfunction "1_1") (pintype "passive"))
    )
    (net (code "34") (name "Net-(D4-A)") (class "Default")
      (node (ref "D4") (pin "1") (pinfunction "A_1") (pintype "passive"))
      (node (ref "R8") (pin "1") (pinfunction "1_1") (pintype "passive"))
    )
    (net (code "35") (name "Net-(D5-A)") (class "Default")
      (node (ref "D5") (pin "1") (pinfunction "A_1") (pintype "passive"))
      (node (ref "R13") (pin "1") (pinfunction "1_1") (pintype "passive"))
    )
    (net (code "36") (name "Net-(D6-A)") (class "Default")
      (node (ref "D6") (pin "1") (pinfunction "A_1") (pintype "passive"))
      (node (ref "R14") (pin "1") (pinfunction "1_1") (pintype "passive"))
    )
    (net (code "37") (name "Net-(D7-A)") (class "Default")
      (node (ref "D7") (pin "1") (pinfunction "A_1") (pintype "passive"))
      (node (ref "R15") (pin "1") (pinfunction "1_1") (pintype "passive"))
    )
    (net (code "38") (name "Net-(D8-A)") (class "Default")
      (node (ref "D8") (pin "1") (pinfunction "A_1") (pintype "passive"))
      (node (ref "R16") (pin "1") (pinfunction "1_1") (pintype "passive"))
    )
    (net (code "39") (name "Net-(D9-A)") (class "Default")
      (node (ref "D9") (pin "1") (pinfunction "A_1") (pintype "passive"))
      (node (ref "R21") (pin "1") (pinfunction "1_1") (pintype "passive"))
    )
    (net (code "40") (name "Net-(D10-A)") (class "Default")
      (node (ref "D10") (pin "1") (pinfunction "A_1") (pintype "passive"))
      (node (ref "R22") (pin "1") (pinfunction "1_1") (pintype "passive"))
    )
    (net (code "41") (name "Net-(D11-A)") (class "Default")
      (node (ref "D11") (pin "1") (pinfunction "A_1") (pintype "passive"))
      (node (ref "R23") (pin "1") (pinfunction "1_1") (pintype "passive"))
    )
    (net (code "42") (name "Net-(D12-A)") (class "Default")
      (node (ref "D12") (pin "1") (pinfunction "A_1") (pintype "passive"))
      (node (ref "R24") (pin "1") (pinfunction "1_1") (pintype "passive"))
    )
    (net (code "43") (name "Net-(D13-A)") (class "Default")
      (node (ref "D13") (pin "1") (pinfunction "A_1") (pintype "passive"))
      (node (ref "R28") (pin "1") (pinfunction "1_1") (pintype "passive"))
    )
    (net (code "44") (name "Net-(D14-A)") (class "Default")
      (node (ref "D14") (pin "1") (pinfunction "A_1") (pintype "passive"))
      (node (ref "R29") (pin "1") (pinfunction "1_1") (pintype "passive"))
    )
    (net (code "45") (name "Net-(D15-K)") (class "Default")
      (node (ref "D15") (pin "2") (pinfunction "K_2") (pintype "passive"))
      (node (ref "R27") (pin "2") (pinfunction "2_2") (pintype "passive"))
    )
  )
)
